# SparkFun-Blynk-Thing.net
KiCad netlist of a schematic drawn in EAGLE
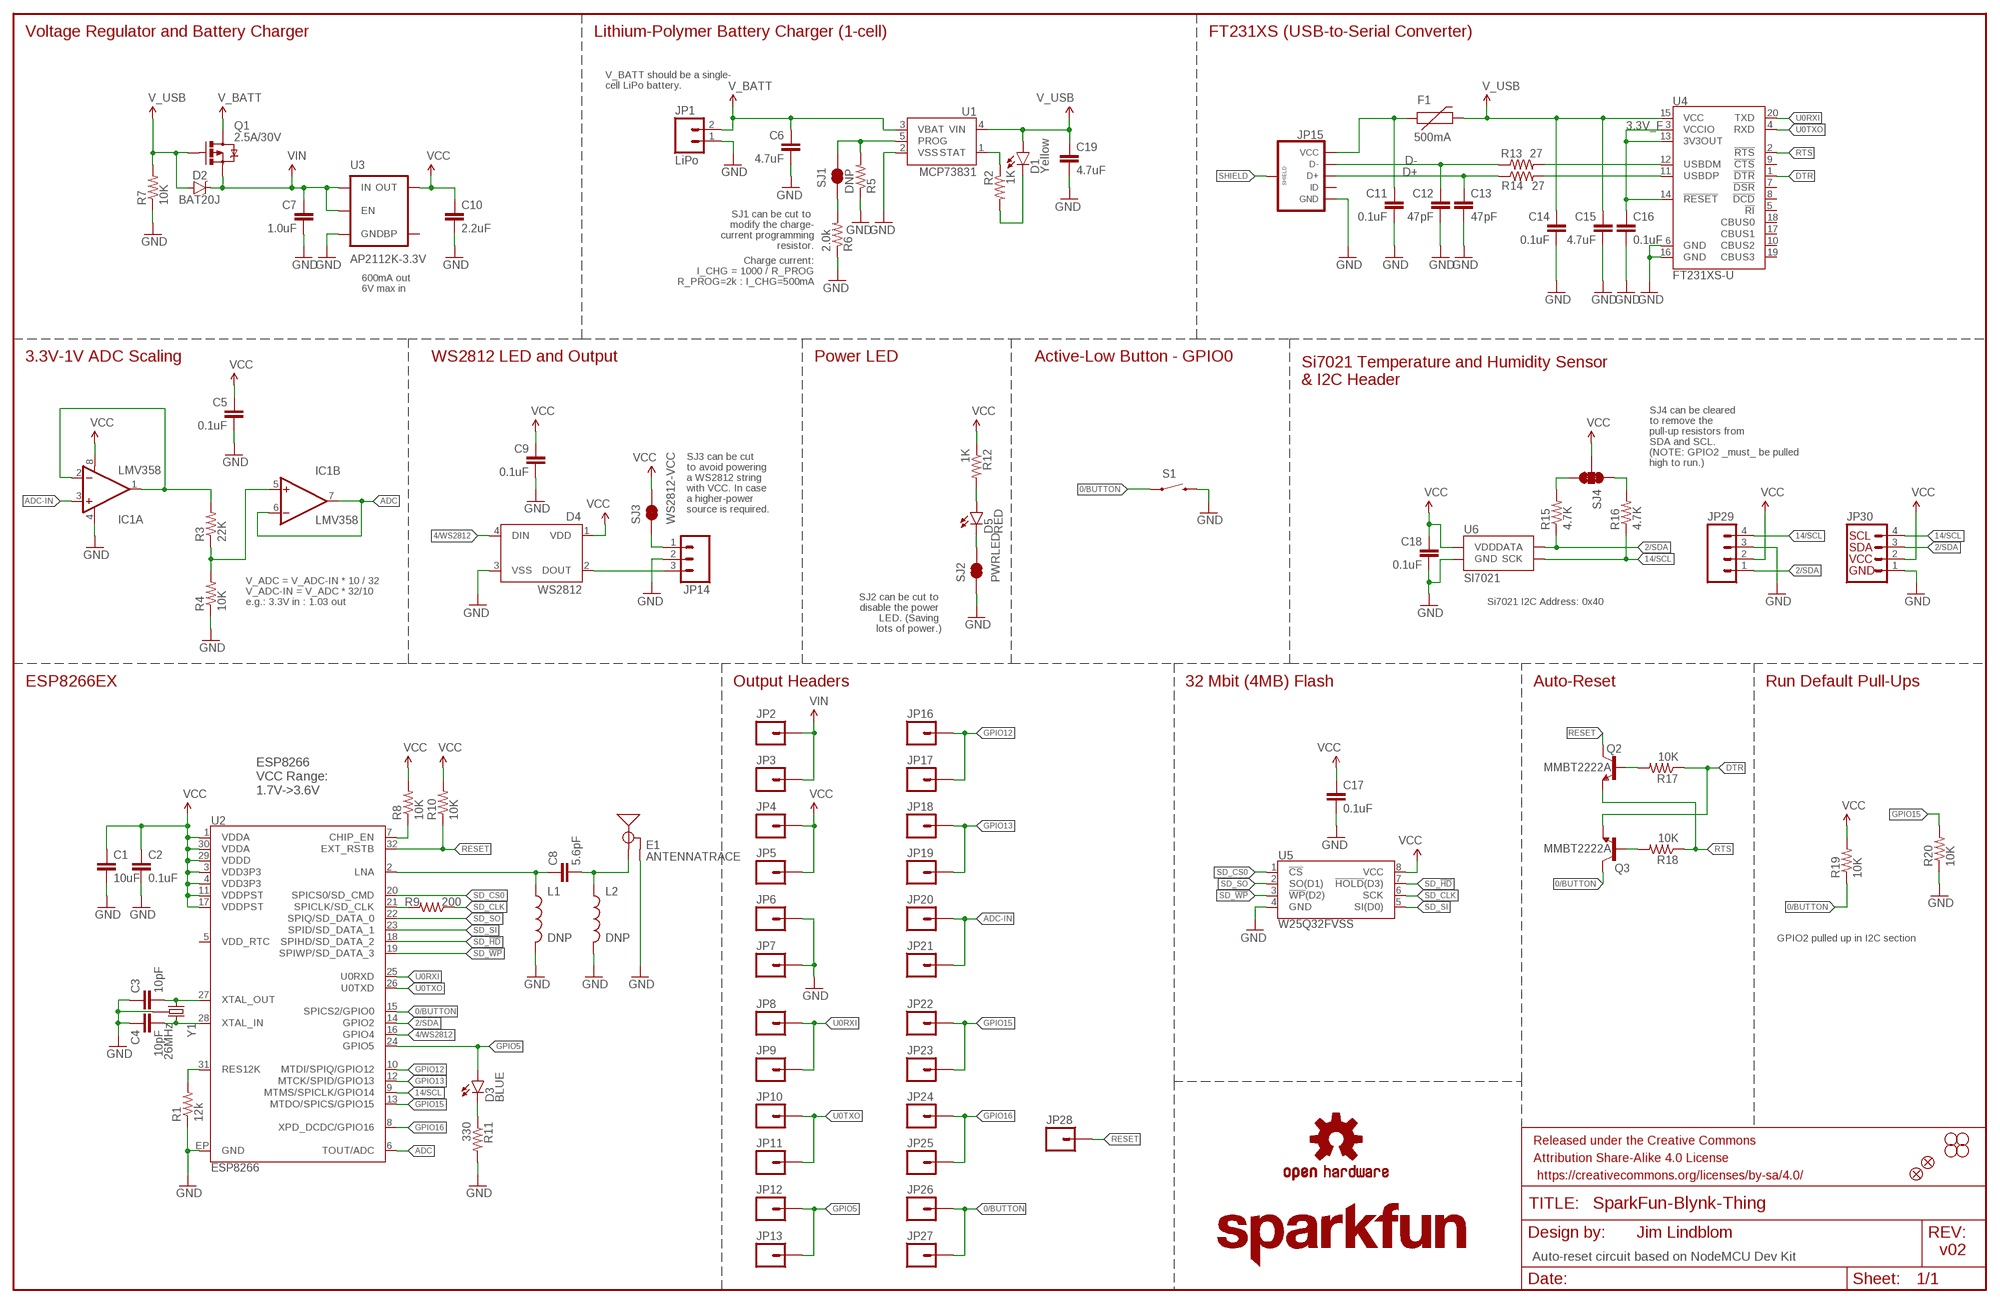
[diagram p0: schematic, sheet 1]

(export (version "E")
  (design (tool "Eeschema 10.0.6"))
  (components
    (comp (ref "C1")
      (value "10uF")
      (footprint "eagle-import:0603-CAP")
      (libsource (lib "eagle-import") (part "10UF-6.3V-20%(0603)"))
    )
    (comp (ref "C2")
      (value "0.1uF")
      (footprint "eagle-import:0603-CAP")
      (libsource (lib "eagle-import") (part "0.1UF-25V(+80/-20%)(0603)"))
    )
    (comp (ref "C3")
      (value "10pF")
      (footprint "eagle-import:0603-CAP")
      (libsource (lib "eagle-import") (part "10PF-50V-5%(0603)"))
    )
    (comp (ref "C4")
      (value "10pF")
      (footprint "eagle-import:0603-CAP")
      (libsource (lib "eagle-import") (part "10PF-50V-5%(0603)"))
    )
    (comp (ref "C5")
      (value "0.1uF")
      (footprint "eagle-import:0603-CAP")
      (libsource (lib "eagle-import") (part "0.1UF-25V(+80/-20%)(0603)"))
    )
    (comp (ref "C6")
      (value "4.7uF")
      (footprint "eagle-import:0603-CAP")
      (libsource (lib "eagle-import") (part "4.7UF-6.3V-10%(0603)0603"))
    )
    (comp (ref "C7")
      (value "1.0uF")
      (footprint "eagle-import:0805-CAP")
      (libsource (lib "eagle-import") (part "1.0UF-25V-+80/-20(0805){dblquote}"))
    )
    (comp (ref "C8")
      (value "5.6pF")
      (footprint "eagle-import:0603-CAP")
      (libsource (lib "eagle-import") (part "CAP0603-CAP"))
    )
    (comp (ref "C9")
      (value "0.1uF")
      (footprint "eagle-import:0603-CAP")
      (libsource (lib "eagle-import") (part "0.1UF-25V(+80/-20%)(0603)"))
    )
    (comp (ref "C10")
      (value "2.2uF")
      (footprint "eagle-import:0603-CAP")
      (libsource (lib "eagle-import") (part "2.2UF-10V-20%(0603)"))
    )
    (comp (ref "C11")
      (value "0.1uF")
      (footprint "eagle-import:0603-CAP")
      (libsource (lib "eagle-import") (part "0.1UF-25V(+80/-20%)(0603)"))
    )
    (comp (ref "C12")
      (value "47pF")
      (footprint "eagle-import:0603-CAP")
      (libsource (lib "eagle-import") (part "47PF-50V-5%(0603)"))
    )
    (comp (ref "C13")
      (value "47pF")
      (footprint "eagle-import:0603-CAP")
      (libsource (lib "eagle-import") (part "47PF-50V-5%(0603)"))
    )
    (comp (ref "C14")
      (value "0.1uF")
      (footprint "eagle-import:0603-CAP")
      (libsource (lib "eagle-import") (part "0.1UF-25V(+80/-20%)(0603)"))
    )
    (comp (ref "C15")
      (value "4.7uF")
      (footprint "eagle-import:0603-CAP")
      (libsource (lib "eagle-import") (part "4.7UF-6.3V-10%(0603)0603"))
    )
    (comp (ref "C16")
      (value "0.1uF")
      (footprint "eagle-import:0603-CAP")
      (libsource (lib "eagle-import") (part "0.1UF-25V(+80/-20%)(0603)"))
    )
    (comp (ref "C17")
      (value "0.1uF")
      (footprint "eagle-import:0603-CAP")
      (libsource (lib "eagle-import") (part "0.1UF-25V(+80/-20%)(0603)"))
    )
    (comp (ref "C18")
      (value "0.1uF")
      (footprint "eagle-import:0603-CAP")
      (libsource (lib "eagle-import") (part "0.1UF-25V(+80/-20%)(0603)"))
    )
    (comp (ref "C19")
      (value "4.7uF")
      (footprint "eagle-import:0603-CAP")
      (libsource (lib "eagle-import") (part "4.7UF-6.3V-10%(0603)0603"))
    )
    (comp (ref "D1")
      (value "Yellow")
      (footprint "eagle-import:LED-0603")
      (libsource (lib "eagle-import") (part "LED-YELLOW0603"))
    )
    (comp (ref "D2")
      (value "BAT20J")
      (footprint "eagle-import:SOD-323")
      (libsource (lib "eagle-import") (part "DIODE-SCHOTTKY-BAT20J"))
    )
    (comp (ref "D3")
      (value "BLUE")
      (footprint "eagle-import:LED-0603")
      (libsource (lib "eagle-import") (part "LED-BLUE0603"))
    )
    (comp (ref "D4")
      (value "WS2812")
      (footprint "eagle-import:WS2812B")
      (libsource (lib "eagle-import") (part "WS2812B"))
    )
    (comp (ref "D5")
      (value "RED")
      (footprint "eagle-import:LED-0603")
      (libsource (lib "eagle-import") (part "LED-RED0603"))
    )
    (comp (ref "E1")
      (value "ANTENNATRACE")
      (footprint "eagle-import:TRACE_ANTENNA_2.4GHZ_25.7MM")
      (libsource (lib "eagle-import") (part "ANTENNATRACE"))
    )
    (comp (ref "F1")
      (value "500mA")
      (footprint "eagle-import:PTC-1206")
      (libsource (lib "eagle-import") (part "PTCSMD"))
    )
    (comp (ref "FID1")
      (value "FIDUCIAL1X2")
      (footprint "eagle-import:FIDUCIAL-1X2")
      (libsource (lib "eagle-import") (part "FIDUCIAL1X2"))
    )
    (comp (ref "FID2")
      (value "FIDUCIAL1X2")
      (footprint "eagle-import:FIDUCIAL-1X2")
      (libsource (lib "eagle-import") (part "FIDUCIAL1X2"))
    )
    (comp (ref "FRAME1")
      (value "FRAME-LEDGER")
      (footprint "eagle-import:CREATIVE_COMMONS")
      (libsource (lib "eagle-import") (part "FRAME-LEDGER"))
    )
    (comp (ref "IC1")
      (value "LMV358")
      (footprint "eagle-import:SO08")
      (fields (field (name "PROD_ID") "IC-09657"))
      (libsource (lib "eagle-import") (part "OPAMP-DUALU"))
    )
    (comp (ref "JP1")
      (value "LiPo")
      (footprint "eagle-import:JST-2-PTH")
      (libsource (lib "eagle-import") (part "M02JST-PTH-2"))
    )
    (comp (ref "JP2")
      (value "M01ALLIGATOR_HALF")
      (footprint "eagle-import:1X01_ALLIGATOR_3MM_HALF")
      (libsource (lib "eagle-import") (part "M01ALLIGATOR_HALF"))
    )
    (comp (ref "JP3")
      (value "M01PTH_NO_SILK_YES_STOP")
      (footprint "eagle-import:1X01_NO_SILK")
      (libsource (lib "eagle-import") (part "M01PTH_NO_SILK_YES_STOP"))
    )
    (comp (ref "JP4")
      (value "M01ALLIGATOR_HALF")
      (footprint "eagle-import:1X01_ALLIGATOR_3MM_HALF")
      (libsource (lib "eagle-import") (part "M01ALLIGATOR_HALF"))
    )
    (comp (ref "JP5")
      (value "M01PTH_NO_SILK_YES_STOP")
      (footprint "eagle-import:1X01_NO_SILK")
      (libsource (lib "eagle-import") (part "M01PTH_NO_SILK_YES_STOP"))
    )
    (comp (ref "JP6")
      (value "M01ALLIGATOR_HALF")
      (footprint "eagle-import:1X01_ALLIGATOR_3MM_HALF")
      (libsource (lib "eagle-import") (part "M01ALLIGATOR_HALF"))
    )
    (comp (ref "JP7")
      (value "M01PTH_NO_SILK_YES_STOP")
      (footprint "eagle-import:1X01_NO_SILK")
      (libsource (lib "eagle-import") (part "M01PTH_NO_SILK_YES_STOP"))
    )
    (comp (ref "JP8")
      (value "M01ALLIGATOR_HALF")
      (footprint "eagle-import:1X01_ALLIGATOR_3MM_HALF")
      (libsource (lib "eagle-import") (part "M01ALLIGATOR_HALF"))
    )
    (comp (ref "JP9")
      (value "M01PTH_NO_SILK_YES_STOP")
      (footprint "eagle-import:1X01_NO_SILK")
      (libsource (lib "eagle-import") (part "M01PTH_NO_SILK_YES_STOP"))
    )
    (comp (ref "JP10")
      (value "M01ALLIGATOR_HALF")
      (footprint "eagle-import:1X01_ALLIGATOR_3MM_HALF")
      (libsource (lib "eagle-import") (part "M01ALLIGATOR_HALF"))
    )
    (comp (ref "JP11")
      (value "M01PTH_NO_SILK_YES_STOP")
      (footprint "eagle-import:1X01_NO_SILK")
      (libsource (lib "eagle-import") (part "M01PTH_NO_SILK_YES_STOP"))
    )
    (comp (ref "JP12")
      (value "M01ALLIGATOR_HALF")
      (footprint "eagle-import:1X01_ALLIGATOR_3MM_HALF")
      (libsource (lib "eagle-import") (part "M01ALLIGATOR_HALF"))
    )
    (comp (ref "JP13")
      (value "M01PTH_NO_SILK_YES_STOP")
      (footprint "eagle-import:1X01_NO_SILK")
      (libsource (lib "eagle-import") (part "M01PTH_NO_SILK_YES_STOP"))
    )
    (comp (ref "JP14")
      (value "M03JST-PTH-VERT")
      (footprint "eagle-import:JST-3-PTH-VERT")
      (libsource (lib "eagle-import") (part "M03JST-PTH-VERT"))
    )
    (comp (ref "JP15")
      (value "USB_MICROB_PLUGCONN-11752")
      (footprint "eagle-import:USB-B-MICRO-SMD_V03")
      (libsource (lib "eagle-import") (part "USB_MICROB_PLUGCONN-11752"))
    )
    (comp (ref "JP16")
      (value "M01ALLIGATOR_HALF")
      (footprint "eagle-import:1X01_ALLIGATOR_3MM_HALF")
      (libsource (lib "eagle-import") (part "M01ALLIGATOR_HALF"))
    )
    (comp (ref "JP17")
      (value "M01PTH_NO_SILK_YES_STOP")
      (footprint "eagle-import:1X01_NO_SILK")
      (libsource (lib "eagle-import") (part "M01PTH_NO_SILK_YES_STOP"))
    )
    (comp (ref "JP18")
      (value "M01ALLIGATOR_HALF")
      (footprint "eagle-import:1X01_ALLIGATOR_3MM_HALF")
      (libsource (lib "eagle-import") (part "M01ALLIGATOR_HALF"))
    )
    (comp (ref "JP19")
      (value "M01PTH_NO_SILK_YES_STOP")
      (footprint "eagle-import:1X01_NO_SILK")
      (libsource (lib "eagle-import") (part "M01PTH_NO_SILK_YES_STOP"))
    )
    (comp (ref "JP20")
      (value "M01ALLIGATOR_HALF")
      (footprint "eagle-import:1X01_ALLIGATOR_3MM_HALF")
      (libsource (lib "eagle-import") (part "M01ALLIGATOR_HALF"))
    )
    (comp (ref "JP21")
      (value "M01PTH_NO_SILK_YES_STOP")
      (footprint "eagle-import:1X01_NO_SILK")
      (libsource (lib "eagle-import") (part "M01PTH_NO_SILK_YES_STOP"))
    )
    (comp (ref "JP22")
      (value "M01ALLIGATOR_HALF")
      (footprint "eagle-import:1X01_ALLIGATOR_3MM_HALF")
      (libsource (lib "eagle-import") (part "M01ALLIGATOR_HALF"))
    )
    (comp (ref "JP23")
      (value "M01PTH_NO_SILK_YES_STOP")
      (footprint "eagle-import:1X01_NO_SILK")
      (libsource (lib "eagle-import") (part "M01PTH_NO_SILK_YES_STOP"))
    )
    (comp (ref "JP24")
      (value "M01ALLIGATOR_HALF")
      (footprint "eagle-import:1X01_ALLIGATOR_3MM_HALF")
      (libsource (lib "eagle-import") (part "M01ALLIGATOR_HALF"))
    )
    (comp (ref "JP25")
      (value "M01PTH_NO_SILK_YES_STOP")
      (footprint "eagle-import:1X01_NO_SILK")
      (libsource (lib "eagle-import") (part "M01PTH_NO_SILK_YES_STOP"))
    )
    (comp (ref "JP26")
      (value "M01ALLIGATOR_HALF")
      (footprint "eagle-import:1X01_ALLIGATOR_3MM_HALF")
      (libsource (lib "eagle-import") (part "M01ALLIGATOR_HALF"))
    )
    (comp (ref "JP27")
      (value "M01PTH_NO_SILK_YES_STOP")
      (footprint "eagle-import:1X01_NO_SILK")
      (libsource (lib "eagle-import") (part "M01PTH_NO_SILK_YES_STOP"))
    )
    (comp (ref "JP28")
      (value "M01PTH_NO_SILK_YES_STOP")
      (footprint "eagle-import:1X01_NO_SILK")
      (libsource (lib "eagle-import") (part "M01PTH_NO_SILK_YES_STOP"))
    )
    (comp (ref "JP29")
      (value "M04JST-PTH-VERT")
      (footprint "eagle-import:JST-4-PTH-VERT")
      (libsource (lib "eagle-import") (part "M04JST-PTH-VERT"))
    )
    (comp (ref "JP30")
      (value "I2C_STANDARD_NO_SILK")
      (footprint "eagle-import:1X04_NO_SILK")
      (libsource (lib "eagle-import") (part "I2C_STANDARD_NO_SILK"))
    )
    (comp (ref "L1")
      (value "DNP")
      (footprint "eagle-import:0603")
      (libsource (lib "eagle-import") (part "INDUCTOR0603"))
    )
    (comp (ref "L2")
      (value "DNP")
      (footprint "eagle-import:0603")
      (libsource (lib "eagle-import") (part "INDUCTOR0603"))
    )
    (comp (ref "LOGO1")
      (value "SFE_LOGO_NAME.2_INCH")
      (footprint "eagle-import:SFE_LOGO_NAME_.2")
      (libsource (lib "eagle-import") (part "SFE_LOGO_NAME.2_INCH"))
    )
    (comp (ref "LOGO2")
      (value "OSHW-LOGOS")
      (footprint "eagle-import:OSHW-LOGO-S")
      (libsource (lib "eagle-import") (part "OSHW-LOGOS"))
    )
    (comp (ref "LOGO3")
      (value "SFE_LOGO_NAME.3_INCH")
      (footprint "eagle-import:SFE_LOGO_NAME_.3")
      (libsource (lib "eagle-import") (part "SFE_LOGO_NAME.3_INCH"))
    )
    (comp (ref "Q1")
      (value "2.5A/30V")
      (footprint "eagle-import:SOT23-3")
      (libsource (lib "eagle-import") (part "MOSFET-PCHANNELDMG2307L"))
    )
    (comp (ref "Q2")
      (value "MMBT2222A")
      (footprint "eagle-import:SOT23-3@1")
      (libsource (lib "eagle-import") (part "TRANSISTOR_NPNMMBT2222A"))
    )
    (comp (ref "Q3")
      (value "MMBT2222A")
      (footprint "eagle-import:SOT23-3@1")
      (libsource (lib "eagle-import") (part "TRANSISTOR_NPNMMBT2222A"))
    )
    (comp (ref "R1")
      (value "12k")
      (footprint "eagle-import:0603-RES")
      (libsource (lib "eagle-import") (part "12KOHM-1/10W-1%(0603)"))
    )
    (comp (ref "R2")
      (value "1K")
      (footprint "eagle-import:0603-RES")
      (libsource (lib "eagle-import") (part "1KOHM-1/10W-1%(0603)"))
    )
    (comp (ref "R3")
      (value "22K")
      (footprint "eagle-import:0603-RES")
      (libsource (lib "eagle-import") (part "22KOHM1/10W1%(0603)"))
    )
    (comp (ref "R4")
      (value "10K")
      (footprint "eagle-import:0603-RES")
      (libsource (lib "eagle-import") (part "10KOHM-1/10W-1%(0603)0603"))
    )
    (comp (ref "R5")
      (value "DNP")
      (footprint "eagle-import:1_6W-RES")
      (libsource (lib "eagle-import") (part "RESISTORPTH-1/6W"))
    )
    (comp (ref "R6")
      (value "2.0k")
      (footprint "eagle-import:0603-RES")
      (libsource (lib "eagle-import") (part "2.0KOHM1/10W5%(0603)"))
    )
    (comp (ref "R7")
      (value "10K")
      (footprint "eagle-import:0603-RES@1")
      (libsource (lib "eagle-import") (part "10KOHM1/10W1%(0603)0603"))
    )
    (comp (ref "R8")
      (value "10K")
      (footprint "eagle-import:0603-RES@1")
      (libsource (lib "eagle-import") (part "10KOHM1/10W1%(0603)0603"))
    )
    (comp (ref "R9")
      (value "200")
      (footprint "eagle-import:0603-RES")
      (libsource (lib "eagle-import") (part "200OHM1/10W1%(0603)"))
    )
    (comp (ref "R10")
      (value "10K")
      (footprint "eagle-import:0603-RES@1")
      (libsource (lib "eagle-import") (part "10KOHM1/10W1%(0603)0603"))
    )
    (comp (ref "R11")
      (value "330")
      (footprint "eagle-import:0603-RES")
      (libsource (lib "eagle-import") (part "330OHM1/10W1%(0603)"))
    )
    (comp (ref "R12")
      (value "1K")
      (footprint "eagle-import:0603-RES")
      (libsource (lib "eagle-import") (part "1KOHM-1/10W-1%(0603)"))
    )
    (comp (ref "R13")
      (value "27")
      (footprint "eagle-import:0603-RES")
      (libsource (lib "eagle-import") (part "27OHM1/10W1%(0603)0603-RES"))
    )
    (comp (ref "R14")
      (value "27")
      (footprint "eagle-import:0603-RES")
      (libsource (lib "eagle-import") (part "27OHM1/10W1%(0603)0603-RES"))
    )
    (comp (ref "R15")
      (value "4.7K")
      (footprint "eagle-import:0603-RES")
      (libsource (lib "eagle-import") (part "4.7KOHM-1/10W-1%(0603)"))
    )
    (comp (ref "R16")
      (value "4.7K")
      (footprint "eagle-import:0603-RES")
      (libsource (lib "eagle-import") (part "4.7KOHM-1/10W-1%(0603)"))
    )
    (comp (ref "R17")
      (value "10K")
      (footprint "eagle-import:0603-RES@1")
      (libsource (lib "eagle-import") (part "10KOHM1/10W1%(0603)0603"))
    )
    (comp (ref "R18")
      (value "10K")
      (footprint "eagle-import:0603-RES@1")
      (libsource (lib "eagle-import") (part "10KOHM1/10W1%(0603)0603"))
    )
    (comp (ref "R19")
      (value "10K")
      (footprint "eagle-import:0603-RES@1")
      (libsource (lib "eagle-import") (part "10KOHM1/10W1%(0603)0603"))
    )
    (comp (ref "R20")
      (value "10K")
      (footprint "eagle-import:0603-RES@1")
      (libsource (lib "eagle-import") (part "10KOHM1/10W1%(0603)0603"))
    )
    (comp (ref "S1")
      (value "SWITCH-MOMENTARY-2SMD-REDUNDANT")
      (footprint "eagle-import:TACTILE-SWITCH-SMD")
      (libsource (lib "eagle-import") (part "SWITCH-MOMENTARY-2SMD-REDUNDANT"))
    )
    (comp (ref "SJ1")
      (value "JUMPER-PAD-2-NC_BY_TRACE")
      (footprint "eagle-import:PAD-JUMPER-2-NC_BY_TRACE_YES_SILK")
      (libsource (lib "eagle-import") (part "JUMPER-PAD-2-NC_BY_TRACE"))
    )
    (comp (ref "SJ2")
      (value "PWRLED")
      (footprint "eagle-import:PAD-JUMPER-2-NC_BY_TRACE_YES_SILK")
      (libsource (lib "eagle-import") (part "JUMPER-PAD-2-NC_BY_TRACE"))
    )
    (comp (ref "SJ3")
      (value "WS2812-VCC")
      (footprint "eagle-import:PAD-JUMPER-2-NC_BY_TRACE_YES_SILK")
      (libsource (lib "eagle-import") (part "JUMPER-PAD-2-NC_BY_TRACE"))
    )
    (comp (ref "SJ4")
      (value "JUMPER-PAD-3-NC_BY_TRACE")
      (footprint "eagle-import:PAD-JUMPER-3-3OF3_NC_BY_TRACE_YES_SILK_FULL_BOX")
      (libsource (lib "eagle-import") (part "JUMPER-PAD-3-NC_BY_TRACE"))
    )
    (comp (ref "STANDOFF1")
      (value "STAND-OFF")
      (footprint "eagle-import:STAND-OFF")
      (libsource (lib "eagle-import") (part "STAND-OFF"))
    )
    (comp (ref "STANDOFF2")
      (value "STAND-OFF")
      (footprint "eagle-import:STAND-OFF")
      (libsource (lib "eagle-import") (part "STAND-OFF"))
    )
    (comp (ref "STANDOFF3")
      (value "STAND-OFF")
      (footprint "eagle-import:STAND-OFF")
      (libsource (lib "eagle-import") (part "STAND-OFF"))
    )
    (comp (ref "STANDOFF4")
      (value "STAND-OFF")
      (footprint "eagle-import:STAND-OFF")
      (libsource (lib "eagle-import") (part "STAND-OFF"))
    )
    (comp (ref "U1")
      (value "MCP73831")
      (footprint "eagle-import:SOT23-5")
      (libsource (lib "eagle-import") (part "MCP73831"))
    )
    (comp (ref "U2")
      (value "ESP8266")
      (footprint "eagle-import:QFN32")
      (fields (field (name "PROD_ID") "IC-12452"))
      (libsource (lib "eagle-import") (part "ESP8266"))
    )
    (comp (ref "U3")
      (value "AP2112K-3.3V")
      (footprint "eagle-import:SOT23-5")
      (libsource (lib "eagle-import") (part "V_REG_LDOSMD"))
    )
    (comp (ref "U4")
      (value "FT231XS-U")
      (footprint "eagle-import:SSOP20_L")
      (libsource (lib "eagle-import") (part "FT231XS"))
    )
    (comp (ref "U5")
      (value "W25Q32FVSS")
      (footprint "eagle-import:SOIC-8")
      (fields (field (name "PROD_ID") "IC-13229"))
      (libsource (lib "eagle-import") (part "W25Q32FVSS"))
    )
    (comp (ref "U6")
      (value "SI7021")
      (footprint "eagle-import:SI7021")
      (libsource (lib "eagle-import") (part "SI7021"))
    )
    (comp (ref "Y1")
      (value "26MHz")
      (footprint "eagle-import:CRYSTAL-SMD-3.2X2.5")
      (libsource (lib "eagle-import") (part "CRYSTAL-GROUNDED3.2X2.5"))
    )
  )
  (nets
    (net (code "1") (name "/3.3V_F") (class "Default")
      (node (ref "C16") (pin "1") (pinfunction "1_1") (pintype "passive"))
      (node (ref "U4") (pin "13") (pinfunction "3V3OUT_13") (pintype "bidirectional"))
      (node (ref "U4") (pin "14") (pinfunction "~{RESET}_14") (pintype "bidirectional"))
      (node (ref "U4") (pin "3") (pinfunction "VCCIO_3") (pintype "bidirectional"))
    )
    (net (code "2") (name "/D+") (class "Default")
      (node (ref "C13") (pin "1") (pinfunction "1_1") (pintype "passive"))
      (node (ref "JP15") (pin "D+") (pinfunction "D+_D+") (pintype "bidirectional"))
      (node (ref "R14") (pin "1") (pinfunction "1_1") (pintype "passive"))
    )
    (net (code "3") (name "/D-") (class "Default")
      (node (ref "C12") (pin "1") (pinfunction "1_1") (pintype "passive"))
      (node (ref "JP15") (pin "D-") (pinfunction "D-_D-") (pintype "bidirectional"))
      (node (ref "R13") (pin "1") (pinfunction "1_1") (pintype "passive"))
    )
    (net (code "4") (name "/SD_~{HD}") (class "Default")
      (node (ref "U2") (pin "18") (pinfunction "SPIHD/SD_DATA_2_18") (pintype "bidirectional"))
      (node (ref "U5") (pin "7") (pinfunction "~{HOLD}(D3)_7") (pintype "bidirectional"))
    )
    (net (code "5") (name "/SD_~{WP}") (class "Default")
      (node (ref "U2") (pin "19") (pinfunction "SPIWP/SD_DATA_3_19") (pintype "bidirectional"))
      (node (ref "U5") (pin "3") (pinfunction "~{WP}(D2)_3") (pintype "bidirectional"))
    )
    (net (code "6") (name "0{slash}BUTTON") (class "Default")
      (node (ref "JP26") (pin "1@2") (pinfunction "1_1@2") (pintype "passive"))
      (node (ref "JP27") (pin "1") (pinfunction "1_1") (pintype "passive"))
      (node (ref "Q3") (pin "3") (pinfunction "C_3") (pintype "passive"))
      (node (ref "R19") (pin "1") (pinfunction "1_1") (pintype "passive"))
      (node (ref "S1") (pin "1") (pinfunction "1_1") (pintype "passive"))
      (node (ref "S1") (pin "2") (pinfunction "1_2") (pintype "passive"))
      (node (ref "U2") (pin "15") (pinfunction "SPICS2/GPIO0_15") (pintype "bidirectional"))
    )
    (net (code "7") (name "2{slash}SDA") (class "Default")
      (node (ref "JP29") (pin "1") (pinfunction "1_1") (pintype "passive"))
      (node (ref "JP30") (pin "3") (pinfunction "3_3") (pintype "passive"))
      (node (ref "R15") (pin "1") (pinfunction "1_1") (pintype "passive"))
      (node (ref "U2") (pin "14") (pinfunction "GPIO2_14") (pintype "bidirectional"))
      (node (ref "U6") (pin "DATA") (pinfunction "DATA_DATA") (pintype "bidirectional"))
    )
    (net (code "8") (name "4{slash}WS2812") (class "Default")
      (node (ref "D4") (pin "4") (pinfunction "DIN_4") (pintype "input"))
      (node (ref "U2") (pin "16") (pinfunction "GPIO4_16") (pintype "bidirectional"))
    )
    (net (code "9") (name "14{slash}SCL") (class "Default")
      (node (ref "JP29") (pin "4") (pinfunction "4_4") (pintype "passive"))
      (node (ref "JP30") (pin "4") (pinfunction "4_4") (pintype "passive"))
      (node (ref "R16") (pin "1") (pinfunction "1_1") (pintype "passive"))
      (node (ref "U2") (pin "9") (pinfunction "MTMS/SPICLK/GPIO14_9") (pintype "bidirectional"))
      (node (ref "U6") (pin "SCK") (pinfunction "SCK_SCK") (pintype "input"))
    )
    (net (code "10") (name "ADC") (class "Default")
      (node (ref "IC1") (pin "6") (pinfunction "-IN_6") (pintype "input"))
      (node (ref "IC1") (pin "7") (pinfunction "OUT_7") (pintype "output"))
      (node (ref "U2") (pin "6") (pinfunction "TOUT/ADC_6") (pintype "bidirectional"))
    )
    (net (code "11") (name "ADC-IN") (class "Default")
      (node (ref "IC1") (pin "3") (pinfunction "+IN_3") (pintype "input"))
      (node (ref "JP20") (pin "1@2") (pinfunction "1_1@2") (pintype "passive"))
      (node (ref "JP21") (pin "1") (pinfunction "1_1") (pintype "passive"))
    )
    (net (code "12") (name "DTR") (class "Default")
      (node (ref "Q3") (pin "2") (pinfunction "E_2") (pintype "passive"))
      (node (ref "R17") (pin "1") (pinfunction "1_1") (pintype "passive"))
      (node (ref "U4") (pin "1") (pinfunction "~{DTR}_1") (pintype "bidirectional"))
    )
    (net (code "13") (name "GND") (class "Default")
      (node (ref "C1") (pin "2") (pinfunction "2_2") (pintype "passive"))
      (node (ref "C10") (pin "2") (pinfunction "2_2") (pintype "passive"))
      (node (ref "C11") (pin "2") (pinfunction "2_2") (pintype "passive"))
      (node (ref "C12") (pin "2") (pinfunction "2_2") (pintype "passive"))
      (node (ref "C13") (pin "2") (pinfunction "2_2") (pintype "passive"))
      (node (ref "C14") (pin "2") (pinfunction "2_2") (pintype "passive"))
      (node (ref "C15") (pin "2") (pinfunction "2_2") (pintype "passive"))
      (node (ref "C16") (pin "2") (pinfunction "2_2") (pintype "passive"))
      (node (ref "C17") (pin "2") (pinfunction "2_2") (pintype "passive"))
      (node (ref "C18") (pin "2") (pinfunction "2_2") (pintype "passive"))
      (node (ref "C19") (pin "2") (pinfunction "2_2") (pintype "passive"))
      (node (ref "C2") (pin "2") (pinfunction "2_2") (pintype "passive"))
      (node (ref "C3") (pin "1") (pinfunction "1_1") (pintype "passive"))
      (node (ref "C4") (pin "1") (pinfunction "1_1") (pintype "passive"))
      (node (ref "C5") (pin "2") (pinfunction "2_2") (pintype "passive"))
      (node (ref "C6") (pin "2") (pinfunction "2_2") (pintype "passive"))
      (node (ref "C7") (pin "2") (pinfunction "2_2") (pintype "passive"))
      (node (ref "C9") (pin "2") (pinfunction "2_2") (pintype "passive"))
      (node (ref "D4") (pin "3") (pinfunction "VSS_3") (pintype "power_in"))
      (node (ref "E1") (pin "GND") (pinfunction "GND_GND") (pintype "bidirectional"))
      (node (ref "E1") (pin "GND2") (pinfunction "GND_GND2") (pintype "bidirectional"))
      (node (ref "IC1") (pin "4") (pinfunction "V-_4") (pintype "power_in"))
      (node (ref "JP1") (pin "1") (pinfunction "1_1") (pintype "passive"))
      (node (ref "JP14") (pin "2") (pinfunction "2_2") (pintype "passive"))
      (node (ref "JP15") (pin "GND") (pinfunction "GND_GND") (pintype "bidirectional"))
      (node (ref "JP29") (pin "3") (pinfunction "3_3") (pintype "passive"))
      (node (ref "JP30") (pin "1") (pinfunction "1_1") (pintype "passive"))
      (node (ref "JP6") (pin "1@2") (pinfunction "1_1@2") (pintype "passive"))
      (node (ref "JP7") (pin "1") (pinfunction "1_1") (pintype "passive"))
      (node (ref "L1") (pin "2") (pinfunction "2_2") (pintype "passive"))
      (node (ref "L2") (pin "2") (pinfunction "2_2") (pintype "passive"))
      (node (ref "R1") (pin "1") (pinfunction "1_1") (pintype "passive"))
      (node (ref "R11") (pin "2") (pinfunction "2_2") (pintype "passive"))
      (node (ref "R20") (pin "1") (pinfunction "1_1") (pintype "passive"))
      (node (ref "R4") (pin "1") (pinfunction "1_1") (pintype "passive"))
      (node (ref "R5") (pin "1") (pinfunction "1_1") (pintype "passive"))
      (node (ref "R6") (pin "1") (pinfunction "1_1") (pintype "passive"))
      (node (ref "R7") (pin "1") (pinfunction "1_1") (pintype "passive"))
      (node (ref "S1") (pin "3") (pinfunction "2_3") (pintype "passive"))
      (node (ref "S1") (pin "4") (pinfunction "2_4") (pintype "passive"))
      (node (ref "SJ2") (pin "1") (pinfunction "1_1") (pintype "passive"))
      (node (ref "U1") (pin "2") (pinfunction "VSS_2") (pintype "power_in"))
      (node (ref "U2") (pin "EP") (pinfunction "GND_EP") (pintype "bidirectional"))
      (node (ref "U3") (pin "2") (pinfunction "GND_2") (pintype "input"))
      (node (ref "U4") (pin "16") (pinfunction "GND_16") (pintype "bidirectional"))
      (node (ref "U4") (pin "6") (pinfunction "GND_6") (pintype "bidirectional"))
      (node (ref "U5") (pin "4") (pinfunction "GND_4") (pintype "bidirectional"))
      (node (ref "U6") (pin "GND") (pinfunction "GND_GND") (pintype "power_in"))
      (node (ref "Y1") (pin "2") (pinfunction "GND_2") (pintype "passive"))
      (node (ref "Y1") (pin "4") (pinfunction "GND_4") (pintype "passive"))
    )
    (net (code "14") (name "GPIO5") (class "Default")
      (node (ref "D3") (pin "A") (pinfunction "A_A") (pintype "passive"))
      (node (ref "JP12") (pin "1@2") (pinfunction "1_1@2") (pintype "passive"))
      (node (ref "JP13") (pin "1") (pinfunction "1_1") (pintype "passive"))
      (node (ref "U2") (pin "24") (pinfunction "GPIO5_24") (pintype "bidirectional"))
    )
    (net (code "15") (name "GPIO12") (class "Default")
      (node (ref "JP16") (pin "1@2") (pinfunction "1_1@2") (pintype "passive"))
      (node (ref "JP17") (pin "1") (pinfunction "1_1") (pintype "passive"))
      (node (ref "U2") (pin "10") (pinfunction "MTDI/SPIQ/GPIO12_10") (pintype "bidirectional"))
    )
    (net (code "16") (name "GPIO13") (class "Default")
      (node (ref "JP18") (pin "1@2") (pinfunction "1_1@2") (pintype "passive"))
      (node (ref "JP19") (pin "1") (pinfunction "1_1") (pintype "passive"))
      (node (ref "U2") (pin "12") (pinfunction "MTCK/SPID/GPIO13_12") (pintype "bidirectional"))
    )
    (net (code "17") (name "GPIO15") (class "Default")
      (node (ref "JP22") (pin "1@2") (pinfunction "1_1@2") (pintype "passive"))
      (node (ref "JP23") (pin "1") (pinfunction "1_1") (pintype "passive"))
      (node (ref "R20") (pin "2") (pinfunction "2_2") (pintype "passive"))
      (node (ref "U2") (pin "13") (pinfunction "MTDO/SPICS/GPIO15_13") (pintype "bidirectional"))
    )
    (net (code "18") (name "GPIO16") (class "Default")
      (node (ref "JP24") (pin "1@2") (pinfunction "1_1@2") (pintype "passive"))
      (node (ref "JP25") (pin "1") (pinfunction "1_1") (pintype "passive"))
      (node (ref "U2") (pin "8") (pinfunction "XPD_DCDC/GPIO16_8") (pintype "bidirectional"))
    )
    (net (code "19") (name "Net-(D1-PadC)") (class "Default")
      (node (ref "D1") (pin "C") (pinfunction "C_C") (pintype "passive"))
      (node (ref "R2") (pin "2") (pinfunction "2_2") (pintype "passive"))
    )
    (net (code "20") (name "Net-(D3-PadC)") (class "Default")
      (node (ref "D3") (pin "C") (pinfunction "C_C") (pintype "passive"))
      (node (ref "R11") (pin "1") (pinfunction "1_1") (pintype "passive"))
    )
    (net (code "21") (name "Net-(D4-DOUT)") (class "Default")
      (node (ref "D4") (pin "2") (pinfunction "DOUT_2") (pintype "output"))
      (node (ref "JP14") (pin "3") (pinfunction "3_3") (pintype "passive"))
    )
    (net (code "22") (name "Net-(D5-PadA)") (class "Default")
      (node (ref "D5") (pin "A") (pinfunction "A_A") (pintype "passive"))
      (node (ref "R12") (pin "2") (pinfunction "2_2") (pintype "passive"))
    )
    (net (code "23") (name "Net-(D5-PadC)") (class "Default")
      (node (ref "D5") (pin "C") (pinfunction "C_C") (pintype "passive"))
      (node (ref "SJ2") (pin "2") (pinfunction "2_2") (pintype "passive"))
    )
    (net (code "24") (name "Net-(E1-SIGNAL)") (class "Default")
      (node (ref "C8") (pin "2") (pinfunction "2_2") (pintype "passive"))
      (node (ref "E1") (pin "ANT") (pinfunction "SIGNAL_ANT") (pintype "bidirectional"))
      (node (ref "L2") (pin "1") (pinfunction "1_1") (pintype "passive"))
    )
    (net (code "25") (name "Net-(IC1A--IN)") (class "Default")
      (node (ref "IC1") (pin "1") (pinfunction "OUT_1") (pintype "output"))
      (node (ref "IC1") (pin "2") (pinfunction "-IN_2") (pintype "input"))
      (node (ref "R3") (pin "2") (pinfunction "2_2") (pintype "passive"))
    )
    (net (code "26") (name "Net-(IC1B-+IN)") (class "Default")
      (node (ref "IC1") (pin "5") (pinfunction "+IN_5") (pintype "input"))
      (node (ref "R3") (pin "1") (pinfunction "1_1") (pintype "passive"))
      (node (ref "R4") (pin "2") (pinfunction "2_2") (pintype "passive"))
    )
    (net (code "27") (name "Net-(JP14-Pad1)") (class "Default")
      (node (ref "JP14") (pin "1") (pinfunction "1_1") (pintype "passive"))
      (node (ref "SJ3") (pin "1") (pinfunction "1_1") (pintype "passive"))
    )
    (net (code "28") (name "Net-(JP15-VCC)") (class "Default")
      (node (ref "C11") (pin "1") (pinfunction "1_1") (pintype "passive"))
      (node (ref "F1") (pin "1") (pinfunction "1_1") (pintype "bidirectional"))
      (node (ref "JP15") (pin "VBUS") (pinfunction "VCC_VBUS") (pintype "bidirectional"))
    )
    (net (code "29") (name "Net-(Q2-B)") (class "Default")
      (node (ref "Q2") (pin "1") (pinfunction "B_1") (pintype "passive"))
      (node (ref "R17") (pin "2") (pinfunction "2_2") (pintype "passive"))
    )
    (net (code "30") (name "Net-(Q3-B)") (class "Default")
      (node (ref "Q3") (pin "1") (pinfunction "B_1") (pintype "passive"))
      (node (ref "R18") (pin "2") (pinfunction "2_2") (pintype "passive"))
    )
    (net (code "31") (name "Net-(R6-Pad2)") (class "Default")
      (node (ref "R6") (pin "2") (pinfunction "2_2") (pintype "passive"))
      (node (ref "SJ1") (pin "1") (pinfunction "1_1") (pintype "passive"))
    )
    (net (code "32") (name "Net-(R15-Pad2)") (class "Default")
      (node (ref "R15") (pin "2") (pinfunction "2_2") (pintype "passive"))
      (node (ref "SJ4") (pin "3") (pinfunction "3_3") (pintype "passive"))
    )
    (net (code "33") (name "Net-(R16-Pad2)") (class "Default")
      (node (ref "R16") (pin "2") (pinfunction "2_2") (pintype "passive"))
      (node (ref "SJ4") (pin "1") (pinfunction "1_1") (pintype "passive"))
    )
    (net (code "34") (name "Net-(U1-PROG)") (class "Default")
      (node (ref "R5") (pin "2") (pinfunction "2_2") (pintype "passive"))
      (node (ref "SJ1") (pin "2") (pinfunction "2_2") (pintype "passive"))
      (node (ref "U1") (pin "5") (pinfunction "PROG_5") (pintype "input"))
    )
    (net (code "35") (name "Net-(U1-STAT)") (class "Default")
      (node (ref "R2") (pin "1") (pinfunction "1_1") (pintype "passive"))
      (node (ref "U1") (pin "1") (pinfunction "STAT_1") (pintype "output"))
    )
    (net (code "36") (name "Net-(U2-CHIP_EN)") (class "Default")
      (node (ref "R8") (pin "1") (pinfunction "1_1") (pintype "passive"))
      (node (ref "U2") (pin "7") (pinfunction "CHIP_EN_7") (pintype "bidirectional"))
    )
    (net (code "37") (name "Net-(U2-LNA)") (class "Default")
      (node (ref "C8") (pin "1") (pinfunction "1_1") (pintype "passive"))
      (node (ref "L1") (pin "1") (pinfunction "1_1") (pintype "passive"))
      (node (ref "U2") (pin "2") (pinfunction "LNA_2") (pintype "bidirectional"))
    )
    (net (code "38") (name "Net-(U2-RES12K)") (class "Default")
      (node (ref "R1") (pin "2") (pinfunction "2_2") (pintype "passive"))
      (node (ref "U2") (pin "31") (pinfunction "RES12K_31") (pintype "bidirectional"))
    )
    (net (code "39") (name "Net-(U2-SPICLK{slash}SD_CLK)") (class "Default")
      (node (ref "R9") (pin "2") (pinfunction "2_2") (pintype "passive"))
      (node (ref "U2") (pin "21") (pinfunction "SPICLK/SD_CLK_21") (pintype "bidirectional"))
    )
    (net (code "40") (name "Net-(U2-XTAL_IN)") (class "Default")
      (node (ref "C4") (pin "2") (pinfunction "2_2") (pintype "passive"))
      (node (ref "U2") (pin "28") (pinfunction "XTAL_IN_28") (pintype "bidirectional"))
      (node (ref "Y1") (pin "3") (pinfunction "2_3") (pintype "passive"))
    )
    (net (code "41") (name "Net-(U2-XTAL_OUT)") (class "Default")
      (node (ref "C3") (pin "2") (pinfunction "2_2") (pintype "passive"))
      (node (ref "U2") (pin "27") (pinfunction "XTAL_OUT_27") (pintype "bidirectional"))
      (node (ref "Y1") (pin "1") (pinfunction "1_1") (pintype "passive"))
    )
    (net (code "42") (name "Net-(U4-USBDM)") (class "Default")
      (node (ref "R13") (pin "2") (pinfunction "2_2") (pintype "passive"))
      (node (ref "U4") (pin "12") (pinfunction "USBDM_12") (pintype "bidirectional"))
    )
    (net (code "43") (name "Net-(U4-USBDP)") (class "Default")
      (node (ref "R14") (pin "2") (pinfunction "2_2") (pintype "passive"))
      (node (ref "U4") (pin "11") (pinfunction "USBDP_11") (pintype "bidirectional"))
    )
    (net (code "44") (name "RESET") (class "Default")
      (node (ref "JP28") (pin "1") (pinfunction "1_1") (pintype "passive"))
      (node (ref "Q2") (pin "3") (pinfunction "C_3") (pintype "passive"))
      (node (ref "R10") (pin "1") (pinfunction "1_1") (pintype "passive"))
      (node (ref "U2") (pin "32") (pinfunction "EXT_RSTB_32") (pintype "bidirectional"))
    )
    (net (code "45") (name "RTS") (class "Default")
      (node (ref "Q2") (pin "2") (pinfunction "E_2") (pintype "passive"))
      (node (ref "R18") (pin "1") (pinfunction "1_1") (pintype "passive"))
      (node (ref "U4") (pin "2") (pinfunction "~{RTS}_2") (pintype "bidirectional"))
    )
    (net (code "46") (name "SD_CLK") (class "Default")
      (node (ref "R9") (pin "1") (pinfunction "1_1") (pintype "passive"))
      (node (ref "U5") (pin "6") (pinfunction "SCK_6") (pintype "bidirectional"))
    )
    (net (code "47") (name "SD_CS0") (class "Default")
      (node (ref "U2") (pin "20") (pinfunction "SPICS0/SD_CMD_20") (pintype "bidirectional"))
      (node (ref "U5") (pin "1") (pinfunction "~{CS}_1") (pintype "bidirectional"))
    )
    (net (code "48") (name "SD_SI") (class "Default")
      (node (ref "U2") (pin "23") (pinfunction "SPID/SD_DATA_1_23") (pintype "bidirectional"))
      (node (ref "U5") (pin "5") (pinfunction "SI(D0)_5") (pintype "bidirectional"))
    )
    (net (code "49") (name "SD_SO") (class "Default")
      (node (ref "U2") (pin "22") (pinfunction "SPIQ/SD_DATA_0_22") (pintype "bidirectional"))
      (node (ref "U5") (pin "2") (pinfunction "SO(D1)_2") (pintype "bidirectional"))
    )
    (net (code "50") (name "SHIELD") (class "Default")
      (node (ref "JP15") (pin "SHIELD1") (pinfunction "SHIELD_SHIELD1") (pintype "bidirectional"))
      (node (ref "JP15") (pin "SHIELD2") (pinfunction "SHIELD_SHIELD2") (pintype "bidirectional"))
      (node (ref "JP15") (pin "SHIELD3") (pinfunction "SHIELD_SHIELD3") (pintype "bidirectional"))
    )
    (net (code "51") (name "U0RXI") (class "Default")
      (node (ref "JP8") (pin "1@2") (pinfunction "1_1@2") (pintype "passive"))
      (node (ref "JP9") (pin "1") (pinfunction "1_1") (pintype "passive"))
      (node (ref "U2") (pin "25") (pinfunction "U0RXD_25") (pintype "bidirectional"))
      (node (ref "U4") (pin "20") (pinfunction "TXD_20") (pintype "bidirectional"))
    )
    (net (code "52") (name "U0TXO") (class "Default")
      (node (ref "JP10") (pin "1@2") (pinfunction "1_1@2") (pintype "passive"))
      (node (ref "JP11") (pin "1") (pinfunction "1_1") (pintype "passive"))
      (node (ref "U2") (pin "26") (pinfunction "U0TXD_26") (pintype "bidirectional"))
      (node (ref "U4") (pin "4") (pinfunction "RXD_4") (pintype "bidirectional"))
    )
    (net (code "53") (name "VCC") (class "Default")
      (node (ref "C1") (pin "1") (pinfunction "1_1") (pintype "passive"))
      (node (ref "C10") (pin "1") (pinfunction "1_1") (pintype "passive"))
      (node (ref "C17") (pin "1") (pinfunction "1_1") (pintype "passive"))
      (node (ref "C18") (pin "1") (pinfunction "1_1") (pintype "passive"))
      (node (ref "C2") (pin "1") (pinfunction "1_1") (pintype "passive"))
      (node (ref "C5") (pin "1") (pinfunction "1_1") (pintype "passive"))
      (node (ref "C9") (pin "1") (pinfunction "1_1") (pintype "passive"))
      (node (ref "D4") (pin "1") (pinfunction "VDD_1") (pintype "power_in"))
      (node (ref "IC1") (pin "8") (pinfunction "V+_8") (pintype "power_in"))
      (node (ref "JP29") (pin "2") (pinfunction "2_2") (pintype "passive"))
      (node (ref "JP30") (pin "2") (pinfunction "2_2") (pintype "passive"))
      (node (ref "JP4") (pin "1@2") (pinfunction "1_1@2") (pintype "passive"))
      (node (ref "JP5") (pin "1") (pinfunction "1_1") (pintype "passive"))
      (node (ref "R10") (pin "2") (pinfunction "2_2") (pintype "passive"))
      (node (ref "R12") (pin "1") (pinfunction "1_1") (pintype "passive"))
      (node (ref "R19") (pin "2") (pinfunction "2_2") (pintype "passive"))
      (node (ref "R8") (pin "2") (pinfunction "2_2") (pintype "passive"))
      (node (ref "SJ3") (pin "2") (pinfunction "2_2") (pintype "passive"))
      (node (ref "SJ4") (pin "2") (pinfunction "2_2") (pintype "passive"))
      (node (ref "U2") (pin "1") (pinfunction "VDDA_1") (pintype "bidirectional"))
      (node (ref "U2") (pin "11") (pinfunction "VDDPST_11") (pintype "bidirectional"))
      (node (ref "U2") (pin "17") (pinfunction "VDDPST_17") (pintype "bidirectional"))
      (node (ref "U2") (pin "29") (pinfunction "VDDD_29") (pintype "bidirectional"))
      (node (ref "U2") (pin "3") (pinfunction "VDD3P3_3") (pintype "bidirectional"))
      (node (ref "U2") (pin "30") (pinfunction "VDDA_30") (pintype "bidirectional"))
      (node (ref "U2") (pin "4") (pinfunction "VDD3P3_4") (pintype "bidirectional"))
      (node (ref "U3") (pin "5") (pinfunction "OUT_5") (pintype "passive"))
      (node (ref "U5") (pin "8") (pinfunction "VCC_8") (pintype "bidirectional"))
      (node (ref "U6") (pin "VDD") (pinfunction "VDD_VDD") (pintype "power_in"))
    )
    (net (code "54") (name "VIN") (class "Default")
      (node (ref "C7") (pin "1") (pinfunction "1_1") (pintype "passive"))
      (node (ref "D2") (pin "C") (pinfunction "C_C") (pintype "passive"))
      (node (ref "JP2") (pin "1@2") (pinfunction "1_1@2") (pintype "passive"))
      (node (ref "JP3") (pin "1") (pinfunction "1_1") (pintype "passive"))
      (node (ref "Q1") (pin "2") (pinfunction "S_2") (pintype "passive"))
      (node (ref "U3") (pin "1") (pinfunction "IN_1") (pintype "input"))
      (node (ref "U3") (pin "3") (pinfunction "EN_3") (pintype "input"))
    )
    (net (code "55") (name "V_BATT") (class "Default")
      (node (ref "C6") (pin "1") (pinfunction "1_1") (pintype "passive"))
      (node (ref "JP1") (pin "2") (pinfunction "2_2") (pintype "passive"))
      (node (ref "Q1") (pin "3") (pinfunction "D_3") (pintype "passive"))
      (node (ref "U1") (pin "3") (pinfunction "VBAT_3") (pintype "power_in"))
    )
    (net (code "56") (name "V_USB") (class "Default")
      (node (ref "C14") (pin "1") (pinfunction "1_1") (pintype "passive"))
      (node (ref "C15") (pin "1") (pinfunction "1_1") (pintype "passive"))
      (node (ref "C19") (pin "1") (pinfunction "1_1") (pintype "passive"))
      (node (ref "D1") (pin "A") (pinfunction "A_A") (pintype "passive"))
      (node (ref "D2") (pin "A") (pinfunction "A_A") (pintype "passive"))
      (node (ref "F1") (pin "2") (pinfunction "2_2") (pintype "bidirectional"))
      (node (ref "Q1") (pin "1") (pinfunction "G_1") (pintype "passive"))
      (node (ref "R7") (pin "2") (pinfunction "2_2") (pintype "passive"))
      (node (ref "U1") (pin "4") (pinfunction "VIN_4") (pintype "power_in"))
      (node (ref "U4") (pin "15") (pinfunction "VCC_15") (pintype "bidirectional"))
    )
    (net (code "57") (name "unconnected-(JP15-PadID)") (class "Default")
      (node (ref "JP15") (pin "ID") (pinfunction "ID_ID") (pintype "bidirectional"))
    )
    (net (code "58") (name "unconnected-(U2-VDD_RTC-Pad5)") (class "Default")
      (node (ref "U2") (pin "5") (pinfunction "VDD_RTC_5") (pintype "bidirectional"))
    )
    (net (code "59") (name "unconnected-(U3-BP-Pad4)") (class "Default")
      (node (ref "U3") (pin "4") (pinfunction "BP_4") (pintype "input"))
    )
    (net (code "60") (name "unconnected-(U4-CBUS0-Pad18)") (class "Default")
      (node (ref "U4") (pin "18") (pinfunction "CBUS0_18") (pintype "bidirectional"))
    )
    (net (code "61") (name "unconnected-(U4-CBUS1-Pad17)") (class "Default")
      (node (ref "U4") (pin "17") (pinfunction "CBUS1_17") (pintype "bidirectional"))
    )
    (net (code "62") (name "unconnected-(U4-CBUS2-Pad10)") (class "Default")
      (node (ref "U4") (pin "10") (pinfunction "CBUS2_10") (pintype "bidirectional"))
    )
    (net (code "63") (name "unconnected-(U4-CBUS3-Pad19)") (class "Default")
      (node (ref "U4") (pin "19") (pinfunction "CBUS3_19") (pintype "bidirectional"))
    )
    (net (code "64") (name "unconnected-(U4-~{CTS}-Pad9)") (class "Default")
      (node (ref "U4") (pin "9") (pinfunction "~{CTS}_9") (pintype "bidirectional"))
    )
    (net (code "65") (name "unconnected-(U4-~{DCD}-Pad8)") (class "Default")
      (node (ref "U4") (pin "8") (pinfunction "~{DCD}_8") (pintype "bidirectional"))
    )
    (net (code "66") (name "unconnected-(U4-~{DSR}-Pad7)") (class "Default")
      (node (ref "U4") (pin "7") (pinfunction "~{DSR}_7") (pintype "bidirectional"))
    )
    (net (code "67") (name "unconnected-(U4-~{RI}-Pad5)") (class "Default")
      (node (ref "U4") (pin "5") (pinfunction "~{RI}_5") (pintype "bidirectional"))
    )
  )
)
